# poorDuino.net
KiCad netlist of a schematic drawn in EAGLE
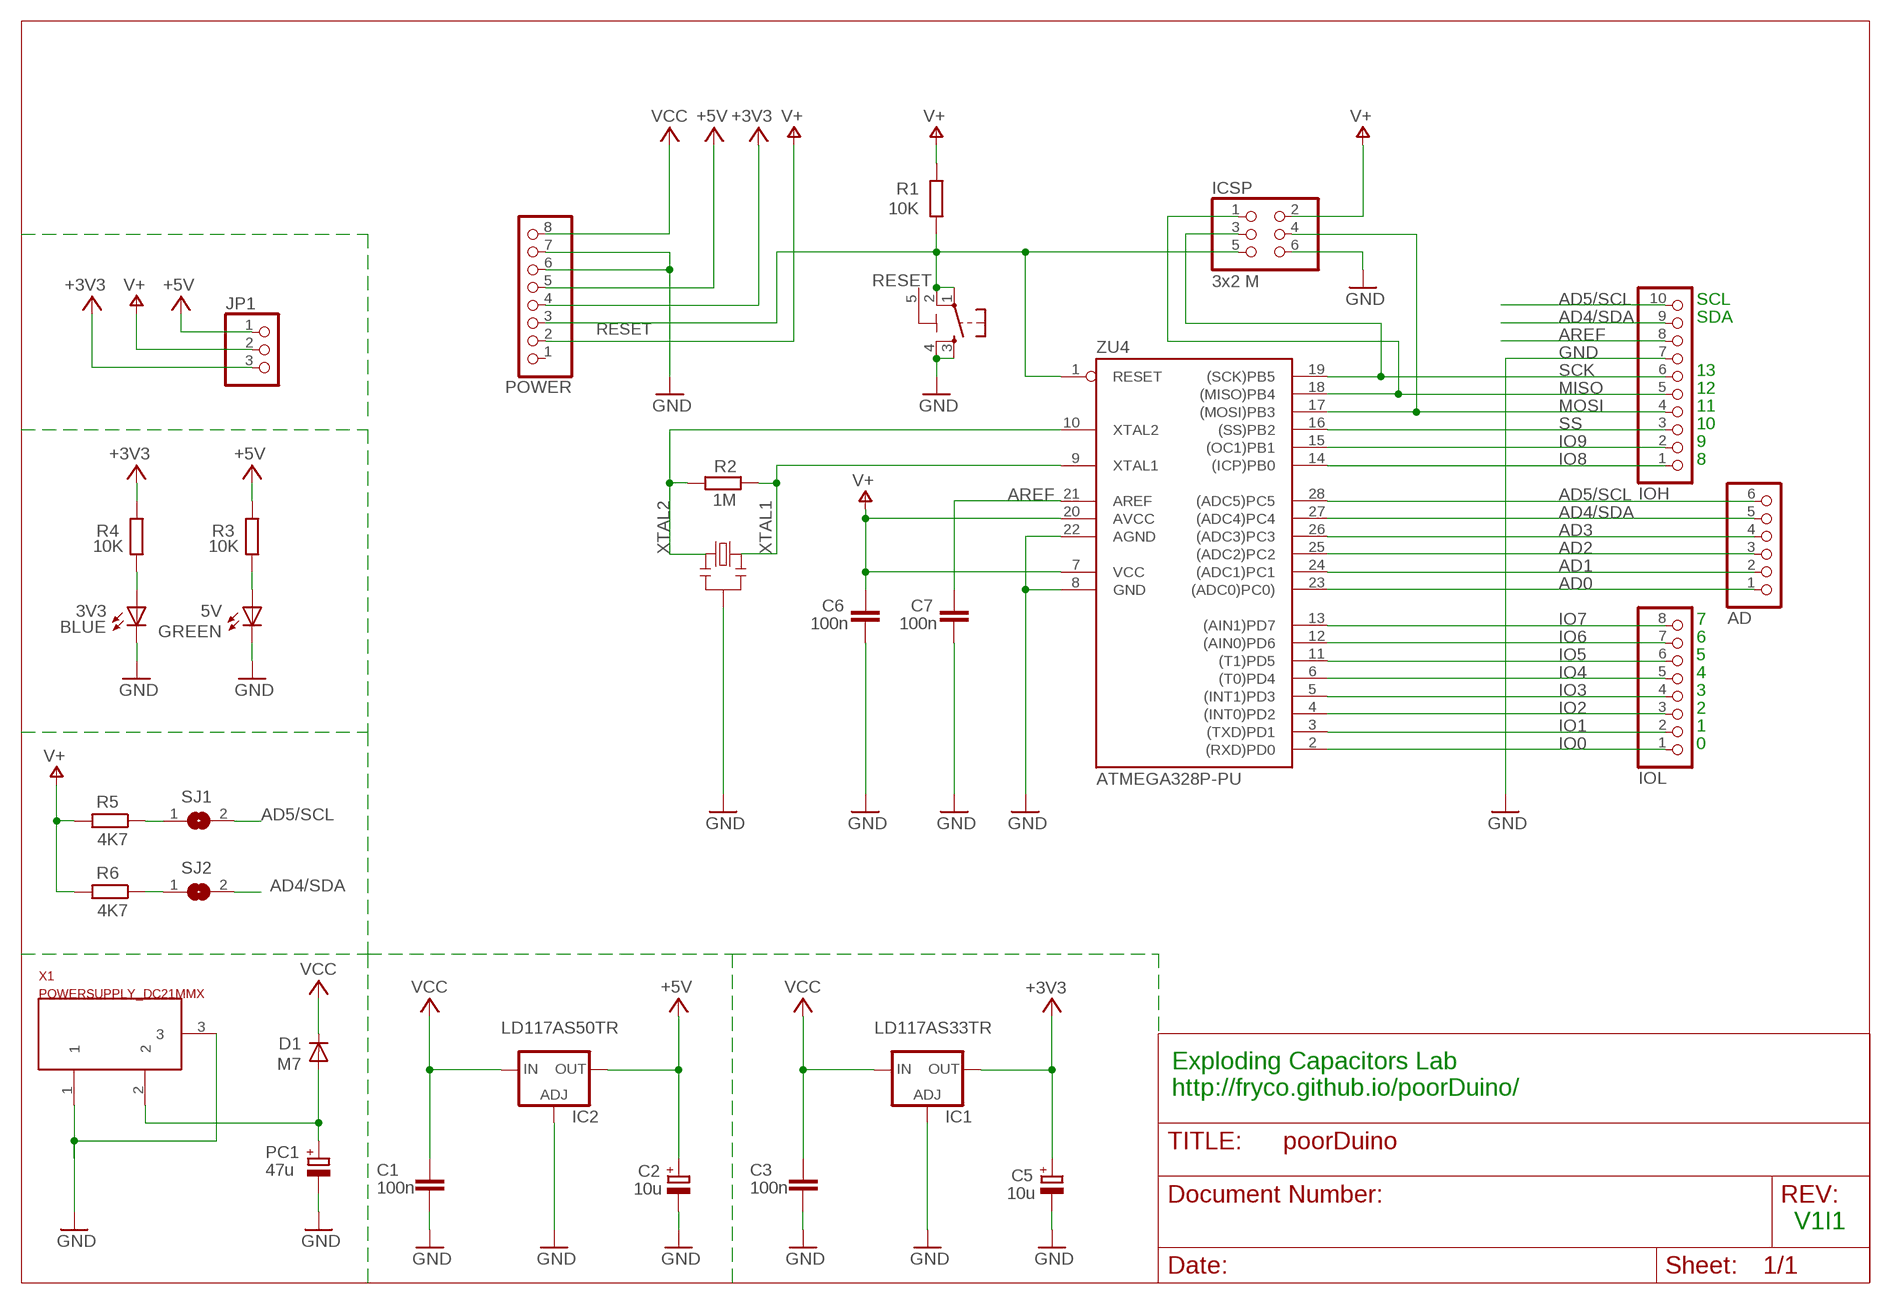
[diagram p0: schematic, sheet 1]

(export (version "E")
  (design (tool "Eeschema 10.0.6"))
  (components
    (comp (ref "3V3")
      (value "BLUE")
      (footprint "eagle-import:CHIP-LED0805")
      (libsource (lib "eagle-import") (part "LEDCHIP-LED0805"))
    )
    (comp (ref "5V")
      (value "GREEN")
      (footprint "eagle-import:CHIP-LED0805")
      (libsource (lib "eagle-import") (part "LEDCHIP-LED0805"))
    )
    (comp (ref "AD")
      (value "6x1F-H8.5")
      (footprint "eagle-import:1X06")
      (libsource (lib "eagle-import") (part "PINHD-1X6"))
    )
    (comp (ref "C1")
      (value "100n")
      (footprint "eagle-import:C0805")
      (libsource (lib "eagle-import") (part "C-EUC0805"))
    )
    (comp (ref "C2")
      (value "10u")
      (footprint "eagle-import:SMC_A")
      (libsource (lib "eagle-import") (part "CPOL-EUSMCA"))
    )
    (comp (ref "C3")
      (value "100n")
      (footprint "eagle-import:C0805")
      (libsource (lib "eagle-import") (part "C-EUC0805"))
    )
    (comp (ref "C5")
      (value "10u")
      (footprint "eagle-import:SMC_A")
      (libsource (lib "eagle-import") (part "CPOL-EUSMCA"))
    )
    (comp (ref "C6")
      (value "100n")
      (footprint "eagle-import:C0805")
      (libsource (lib "eagle-import") (part "C-EUC0805"))
    )
    (comp (ref "C7")
      (value "100n")
      (footprint "eagle-import:C0805")
      (libsource (lib "eagle-import") (part "C-EUC0805"))
    )
    (comp (ref "D1")
      (value "M7")
      (footprint "eagle-import:SMB")
      (libsource (lib "eagle-import") (part "DIODE-SMB"))
    )
    (comp (ref "IC1")
      (value "LD117AS33TR")
      (footprint "eagle-import:SOT223")
      (libsource (lib "eagle-import") (part "LD117A?S33TR"))
    )
    (comp (ref "IC2")
      (value "LD117AS50TR")
      (footprint "eagle-import:SOT223")
      (libsource (lib "eagle-import") (part "LD117A?S50TR"))
    )
    (comp (ref "ICSP")
      (value "3x2 M")
      (footprint "eagle-import:2X03")
      (libsource (lib "eagle-import") (part "PINHD-2X3"))
    )
    (comp (ref "IOH")
      (value "10x1F-H8.5")
      (footprint "eagle-import:1X10")
      (libsource (lib "eagle-import") (part "PINHD-1X10_ARD"))
    )
    (comp (ref "IOL")
      (value "8x1F-H8.5")
      (footprint "eagle-import:1X08")
      (libsource (lib "eagle-import") (part "PINHD-1X8"))
    )
    (comp (ref "JP1")
      (value "PINHD-1X3")
      (footprint "eagle-import:1X03")
      (libsource (lib "eagle-import") (part "PINHD-1X3"))
    )
    (comp (ref "PC1")
      (value "47u")
      (footprint "eagle-import:PANASONIC_D")
      (libsource (lib "eagle-import") (part "CPOL-EUD"))
    )
    (comp (ref "POWER")
      (value "8x1F-H8.5")
      (footprint "eagle-import:1X08")
      (libsource (lib "eagle-import") (part "PINHD-1X8"))
    )
    (comp (ref "R1")
      (value "10K")
      (footprint "eagle-import:R0805")
      (libsource (lib "eagle-import") (part "R-EU_R0805"))
    )
    (comp (ref "R2")
      (value "1M")
      (footprint "eagle-import:R0805")
      (libsource (lib "eagle-import") (part "R-EU_R0805"))
    )
    (comp (ref "R3")
      (value "10K")
      (footprint "eagle-import:R0805")
      (libsource (lib "eagle-import") (part "R-EU_R0805"))
    )
    (comp (ref "R4")
      (value "10K")
      (footprint "eagle-import:R0805")
      (libsource (lib "eagle-import") (part "R-EU_R0805"))
    )
    (comp (ref "R5")
      (value "4K7")
      (footprint "eagle-import:R0805")
      (libsource (lib "eagle-import") (part "R-EU_R0805"))
    )
    (comp (ref "R6")
      (value "4K7")
      (footprint "eagle-import:R0805")
      (libsource (lib "eagle-import") (part "R-EU_R0805"))
    )
    (comp (ref "RESET")
      (value "TS42031-160R-TR-7260")
      (footprint "eagle-import:TS42")
      (libsource (lib "eagle-import") (part "TS42"))
    )
    (comp (ref "SJ1") (value "SJ") (footprint "eagle-import:SJ") (libsource (lib "eagle-import") (part "SJ")))
    (comp (ref "SJ2") (value "SJ") (footprint "eagle-import:SJ") (libsource (lib "eagle-import") (part "SJ")))
    (comp (ref "X1")
      (value "POWERSUPPLY_DC21MMX")
      (footprint "eagle-import:POWERSUPPLY_DC-21MM")
      (libsource (lib "eagle-import") (part "POWERSUPPLY_DC21MMX"))
    )
    (comp (ref "Y2")
      (value "CSTCE16M0V53-R0 16MHZ")
      (footprint "eagle-import:RESONATOR")
      (libsource (lib "eagle-import") (part "RESONATORMU"))
    )
    (comp (ref "ZU4")
      (value "ATMEGA328P-PU")
      (footprint "eagle-import:DIL28-3")
      (libsource (lib "eagle-import") (part "ATMEGA328P-PU"))
    )
  )
  (nets
    (net (code "1") (name "+3V3") (class "Default")
      (node (ref "C5") (pin "+") (pinfunction "+_+") (pintype "passive"))
      (node (ref "IC1") (pin "4") (pinfunction "OUT_4") (pintype "passive"))
      (node (ref "JP1") (pin "3") (pinfunction "3_3") (pintype "passive"))
      (node (ref "POWER") (pin "4") (pinfunction "4_4") (pintype "passive"))
      (node (ref "R4") (pin "1") (pinfunction "1_1") (pintype "passive"))
    )
    (net (code "2") (name "+5V") (class "Default")
      (node (ref "C2") (pin "+") (pinfunction "+_+") (pintype "passive"))
      (node (ref "IC2") (pin "4") (pinfunction "OUT_4") (pintype "passive"))
      (node (ref "JP1") (pin "1") (pinfunction "1_1") (pintype "passive"))
      (node (ref "POWER") (pin "5") (pinfunction "5_5") (pintype "passive"))
      (node (ref "R3") (pin "1") (pinfunction "1_1") (pintype "passive"))
    )
    (net (code "3") (name "/5-GND") (class "Default")
      (node (ref "RESET") (pin "5") (pinfunction "5-GND_5") (pintype "power_in"))
    )
    (net (code "4") (name "/AD0") (class "Default")
      (node (ref "AD") (pin "1") (pinfunction "1_1") (pintype "passive"))
      (node (ref "ZU4") (pin "23") (pinfunction "(ADC0)PC0)_23") (pintype "bidirectional"))
    )
    (net (code "5") (name "/AD1") (class "Default")
      (node (ref "AD") (pin "2") (pinfunction "2_2") (pintype "passive"))
      (node (ref "ZU4") (pin "24") (pinfunction "(ADC1)PC1_24") (pintype "bidirectional"))
    )
    (net (code "6") (name "/AD2") (class "Default")
      (node (ref "AD") (pin "3") (pinfunction "3_3") (pintype "passive"))
      (node (ref "ZU4") (pin "25") (pinfunction "(ADC2)PC2_25") (pintype "bidirectional"))
    )
    (net (code "7") (name "/AD3") (class "Default")
      (node (ref "AD") (pin "4") (pinfunction "4_4") (pintype "passive"))
      (node (ref "ZU4") (pin "26") (pinfunction "(ADC3)PC3_26") (pintype "bidirectional"))
    )
    (net (code "8") (name "/AD4{slash}SDA") (class "Default")
      (node (ref "AD") (pin "5") (pinfunction "5_5") (pintype "passive"))
      (node (ref "IOH") (pin "9") (pinfunction "9_9") (pintype "passive"))
      (node (ref "SJ2") (pin "2") (pinfunction "2_2") (pintype "passive"))
      (node (ref "ZU4") (pin "27") (pinfunction "(ADC4)PC4_27") (pintype "bidirectional"))
    )
    (net (code "9") (name "/AD5{slash}SCL") (class "Default")
      (node (ref "AD") (pin "6") (pinfunction "6_6") (pintype "passive"))
      (node (ref "IOH") (pin "10") (pinfunction "10_10") (pintype "passive"))
      (node (ref "SJ1") (pin "2") (pinfunction "2_2") (pintype "passive"))
      (node (ref "ZU4") (pin "28") (pinfunction "(ADC5)PC5_28") (pintype "bidirectional"))
    )
    (net (code "10") (name "/AREF") (class "Default")
      (node (ref "C7") (pin "2") (pinfunction "2_2") (pintype "passive"))
      (node (ref "IOH") (pin "8") (pinfunction "8_8") (pintype "passive"))
      (node (ref "ZU4") (pin "21") (pinfunction "AREF_21") (pintype "passive"))
    )
    (net (code "11") (name "/IO0") (class "Default")
      (node (ref "IOL") (pin "1") (pinfunction "1_1") (pintype "passive"))
      (node (ref "ZU4") (pin "2") (pinfunction "(RXD)PD0_2") (pintype "bidirectional"))
    )
    (net (code "12") (name "/IO1") (class "Default")
      (node (ref "IOL") (pin "2") (pinfunction "2_2") (pintype "passive"))
      (node (ref "ZU4") (pin "3") (pinfunction "(TXD)PD1_3") (pintype "bidirectional"))
    )
    (net (code "13") (name "/IO2") (class "Default")
      (node (ref "IOL") (pin "3") (pinfunction "3_3") (pintype "passive"))
      (node (ref "ZU4") (pin "4") (pinfunction "(INT0)PD2_4") (pintype "bidirectional"))
    )
    (net (code "14") (name "/IO3") (class "Default")
      (node (ref "IOL") (pin "4") (pinfunction "4_4") (pintype "passive"))
      (node (ref "ZU4") (pin "5") (pinfunction "(INT1)PD3_5") (pintype "bidirectional"))
    )
    (net (code "15") (name "/IO4") (class "Default")
      (node (ref "IOL") (pin "5") (pinfunction "5_5") (pintype "passive"))
      (node (ref "ZU4") (pin "6") (pinfunction "(T0)PD4_6") (pintype "bidirectional"))
    )
    (net (code "16") (name "/IO5") (class "Default")
      (node (ref "IOL") (pin "6") (pinfunction "6_6") (pintype "passive"))
      (node (ref "ZU4") (pin "11") (pinfunction "(T1)PD5_11") (pintype "bidirectional"))
    )
    (net (code "17") (name "/IO6") (class "Default")
      (node (ref "IOL") (pin "7") (pinfunction "7_7") (pintype "passive"))
      (node (ref "ZU4") (pin "12") (pinfunction "(AIN0)PD6_12") (pintype "bidirectional"))
    )
    (net (code "18") (name "/IO7") (class "Default")
      (node (ref "IOL") (pin "8") (pinfunction "8_8") (pintype "passive"))
      (node (ref "ZU4") (pin "13") (pinfunction "(AIN1)PD7_13") (pintype "bidirectional"))
    )
    (net (code "19") (name "/IO8") (class "Default")
      (node (ref "IOH") (pin "1") (pinfunction "1_1") (pintype "passive"))
      (node (ref "ZU4") (pin "14") (pinfunction "(ICP)PB0_14") (pintype "bidirectional"))
    )
    (net (code "20") (name "/IO9") (class "Default")
      (node (ref "IOH") (pin "2") (pinfunction "2_2") (pintype "passive"))
      (node (ref "ZU4") (pin "15") (pinfunction "(OC1)PB1_15") (pintype "bidirectional"))
    )
    (net (code "21") (name "/MISO") (class "Default")
      (node (ref "ICSP") (pin "1") (pinfunction "1_1") (pintype "passive"))
      (node (ref "IOH") (pin "5") (pinfunction "5_5") (pintype "passive"))
      (node (ref "ZU4") (pin "18") (pinfunction "(MISO)PB4_18") (pintype "bidirectional"))
    )
    (net (code "22") (name "/MOSI") (class "Default")
      (node (ref "ICSP") (pin "4") (pinfunction "4_4") (pintype "passive"))
      (node (ref "IOH") (pin "4") (pinfunction "4_4") (pintype "passive"))
      (node (ref "ZU4") (pin "17") (pinfunction "(MOSI)PB3_17") (pintype "bidirectional"))
    )
    (net (code "24") (name "/RESET") (class "Default")
      (node (ref "ICSP") (pin "5") (pinfunction "5_5") (pintype "passive"))
      (node (ref "POWER") (pin "3") (pinfunction "3_3") (pintype "passive"))
      (node (ref "R1") (pin "1") (pinfunction "1_1") (pintype "passive"))
      (node (ref "RESET") (pin "1") (pinfunction "1_1") (pintype "passive"))
      (node (ref "RESET") (pin "2") (pinfunction "2_2") (pintype "passive"))
      (node (ref "ZU4") (pin "1") (pinfunction "RESET_1") (pintype "input"))
    )
    (net (code "25") (name "/SCK") (class "Default")
      (node (ref "ICSP") (pin "3") (pinfunction "3_3") (pintype "passive"))
      (node (ref "IOH") (pin "6") (pinfunction "6_6") (pintype "passive"))
      (node (ref "ZU4") (pin "19") (pinfunction "(SCK)PB5_19") (pintype "bidirectional"))
    )
    (net (code "26") (name "/SS") (class "Default")
      (node (ref "IOH") (pin "3") (pinfunction "3_3") (pintype "passive"))
      (node (ref "ZU4") (pin "16") (pinfunction "(SS)PB2_16") (pintype "bidirectional"))
    )
    (net (code "27") (name "/XTAL1") (class "Default")
      (node (ref "R2") (pin "1") (pinfunction "1_1") (pintype "passive"))
      (node (ref "Y2") (pin "3") (pinfunction "3_3") (pintype "passive"))
      (node (ref "ZU4") (pin "9") (pinfunction "XTAL1_9") (pintype "bidirectional"))
    )
    (net (code "28") (name "/XTAL2") (class "Default")
      (node (ref "R2") (pin "2") (pinfunction "2_2") (pintype "passive"))
      (node (ref "Y2") (pin "1") (pinfunction "1_1") (pintype "passive"))
      (node (ref "ZU4") (pin "10") (pinfunction "XTAL2_10") (pintype "bidirectional"))
    )
    (net (code "29") (name "GND") (class "Default")
      (node (ref "3V3") (pin "C") (pinfunction "C_C") (pintype "passive"))
      (node (ref "5V") (pin "C") (pinfunction "C_C") (pintype "passive"))
      (node (ref "C1") (pin "1") (pinfunction "1_1") (pintype "passive"))
      (node (ref "C2") (pin "-") (pinfunction "-_-") (pintype "passive"))
      (node (ref "C3") (pin "1") (pinfunction "1_1") (pintype "passive"))
      (node (ref "C5") (pin "-") (pinfunction "-_-") (pintype "passive"))
      (node (ref "C6") (pin "1") (pinfunction "1_1") (pintype "passive"))
      (node (ref "C7") (pin "1") (pinfunction "1_1") (pintype "passive"))
      (node (ref "IC1") (pin "1") (pinfunction "ADJ_1") (pintype "input"))
      (node (ref "IC2") (pin "1") (pinfunction "ADJ_1") (pintype "input"))
      (node (ref "ICSP") (pin "6") (pinfunction "6_6") (pintype "passive"))
      (node (ref "IOH") (pin "7") (pinfunction "7_7") (pintype "passive"))
      (node (ref "PC1") (pin "-") (pinfunction "-_-") (pintype "passive"))
      (node (ref "POWER") (pin "6") (pinfunction "6_6") (pintype "passive"))
      (node (ref "POWER") (pin "7") (pinfunction "7_7") (pintype "passive"))
      (node (ref "RESET") (pin "3") (pinfunction "3_3") (pintype "passive"))
      (node (ref "RESET") (pin "4") (pinfunction "4_4") (pintype "passive"))
      (node (ref "X1") (pin "1") (pinfunction "1_1") (pintype "power_in"))
      (node (ref "X1") (pin "3") (pinfunction "3_3") (pintype "power_in"))
      (node (ref "Y2") (pin "2") (pinfunction "2_2") (pintype "passive"))
      (node (ref "ZU4") (pin "22") (pinfunction "AGND_22") (pintype "power_in"))
      (node (ref "ZU4") (pin "8") (pinfunction "GND_8") (pintype "power_in"))
    )
    (net (code "30") (name "Net-(3V3-PadA)") (class "Default")
      (node (ref "3V3") (pin "A") (pinfunction "A_A") (pintype "passive"))
      (node (ref "R4") (pin "2") (pinfunction "2_2") (pintype "passive"))
    )
    (net (code "31") (name "Net-(5V-PadA)") (class "Default")
      (node (ref "5V") (pin "A") (pinfunction "A_A") (pintype "passive"))
      (node (ref "R3") (pin "2") (pinfunction "2_2") (pintype "passive"))
    )
    (net (code "32") (name "Net-(D1-PadA)") (class "Default")
      (node (ref "D1") (pin "A") (pinfunction "A_A") (pintype "passive"))
      (node (ref "PC1") (pin "+") (pinfunction "+_+") (pintype "passive"))
      (node (ref "X1") (pin "2") (pinfunction "2_2") (pintype "power_in"))
    )
    (net (code "33") (name "Net-(R5-Pad1)") (class "Default")
      (node (ref "R5") (pin "1") (pinfunction "1_1") (pintype "passive"))
      (node (ref "SJ1") (pin "1") (pinfunction "1_1") (pintype "passive"))
    )
    (net (code "34") (name "Net-(R6-Pad1)") (class "Default")
      (node (ref "R6") (pin "1") (pinfunction "1_1") (pintype "passive"))
      (node (ref "SJ2") (pin "1") (pinfunction "1_1") (pintype "passive"))
    )
    (net (code "35") (name "V+") (class "Default")
      (node (ref "C6") (pin "2") (pinfunction "2_2") (pintype "passive"))
      (node (ref "ICSP") (pin "2") (pinfunction "2_2") (pintype "passive"))
      (node (ref "JP1") (pin "2") (pinfunction "2_2") (pintype "passive"))
      (node (ref "POWER") (pin "2") (pinfunction "2_2") (pintype "passive"))
      (node (ref "R1") (pin "2") (pinfunction "2_2") (pintype "passive"))
      (node (ref "R5") (pin "2") (pinfunction "2_2") (pintype "passive"))
      (node (ref "R6") (pin "2") (pinfunction "2_2") (pintype "passive"))
      (node (ref "ZU4") (pin "20") (pinfunction "AVCC_20") (pintype "power_in"))
      (node (ref "ZU4") (pin "7") (pinfunction "VCC_7") (pintype "power_in"))
    )
    (net (code "36") (name "VCC") (class "Default")
      (node (ref "C1") (pin "2") (pinfunction "2_2") (pintype "passive"))
      (node (ref "C3") (pin "2") (pinfunction "2_2") (pintype "passive"))
      (node (ref "D1") (pin "C") (pinfunction "C_C") (pintype "passive"))
      (node (ref "IC1") (pin "3") (pinfunction "IN_3") (pintype "input"))
      (node (ref "IC2") (pin "3") (pinfunction "IN_3") (pintype "input"))
      (node (ref "POWER") (pin "8") (pinfunction "8_8") (pintype "passive"))
    )
    (net (code "37") (name "unconnected-(POWER-Pad1)") (class "Default")
      (node (ref "POWER") (pin "1") (pinfunction "1_1") (pintype "passive"))
    )
  )
)
